# Sheet1.net
KiCad netlist of a schematic drawn in Altium Designer
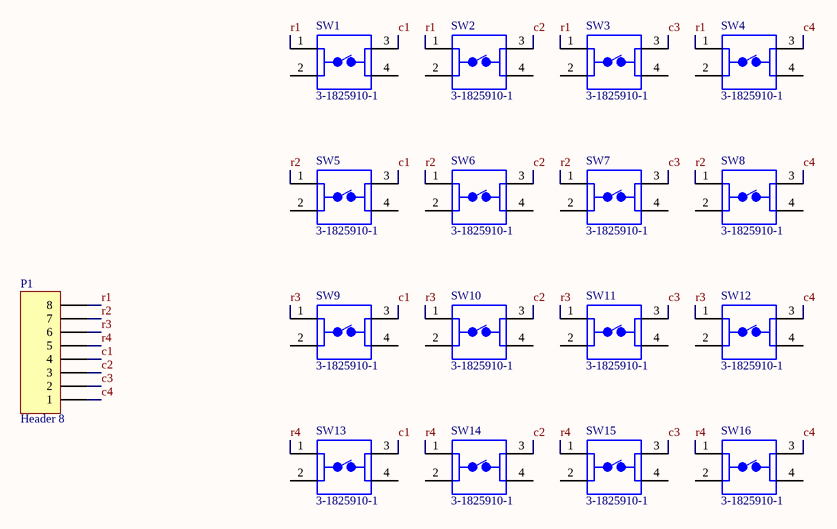
[diagram p0: Sheet1.SchDoc]

(export (version "E")
  (design (tool "Eeschema 10.0.6"))
  (components
    (comp (ref "P1")
      (value "Header 8")
      (footprint "HDR1X8")
      (description "Header, 8-Pin")
      (fields (field (name "PUBLISHER") "Altium Limited"))
      (libsource (lib "Miscellaneous Connectors") (part "Header 8"))
    )
    (comp (ref "SW1")
      (value "3-1825910-1")
      (footprint "TE_3-1825910-1")
      (description "Switch Push Button OFF _ON_ SPST Round Button 0.05A 24VDC Momentary Contact PC Pins Thru-Hole")
      (fields (field (name "MF") "TE Connectivity"))
      (libsource (lib "Schlib1") (part "3-1825910-1"))
    )
    (comp (ref "SW2")
      (value "3-1825910-1")
      (footprint "TE_3-1825910-1")
      (description "Switch Push Button OFF _ON_ SPST Round Button 0.05A 24VDC Momentary Contact PC Pins Thru-Hole")
      (fields (field (name "MF") "TE Connectivity"))
      (libsource (lib "Schlib1") (part "3-1825910-1"))
    )
    (comp (ref "SW3")
      (value "3-1825910-1")
      (footprint "TE_3-1825910-1")
      (description "Switch Push Button OFF _ON_ SPST Round Button 0.05A 24VDC Momentary Contact PC Pins Thru-Hole")
      (fields (field (name "MF") "TE Connectivity"))
      (libsource (lib "Schlib1") (part "3-1825910-1"))
    )
    (comp (ref "SW4")
      (value "3-1825910-1")
      (footprint "TE_3-1825910-1")
      (description "Switch Push Button OFF _ON_ SPST Round Button 0.05A 24VDC Momentary Contact PC Pins Thru-Hole")
      (fields (field (name "MF") "TE Connectivity"))
      (libsource (lib "Schlib1") (part "3-1825910-1"))
    )
    (comp (ref "SW5")
      (value "3-1825910-1")
      (footprint "TE_3-1825910-1")
      (description "Switch Push Button OFF _ON_ SPST Round Button 0.05A 24VDC Momentary Contact PC Pins Thru-Hole")
      (fields (field (name "MF") "TE Connectivity"))
      (libsource (lib "Schlib1") (part "3-1825910-1"))
    )
    (comp (ref "SW6")
      (value "3-1825910-1")
      (footprint "TE_3-1825910-1")
      (description "Switch Push Button OFF _ON_ SPST Round Button 0.05A 24VDC Momentary Contact PC Pins Thru-Hole")
      (fields (field (name "MF") "TE Connectivity"))
      (libsource (lib "Schlib1") (part "3-1825910-1"))
    )
    (comp (ref "SW7")
      (value "3-1825910-1")
      (footprint "TE_3-1825910-1")
      (description "Switch Push Button OFF _ON_ SPST Round Button 0.05A 24VDC Momentary Contact PC Pins Thru-Hole")
      (fields (field (name "MF") "TE Connectivity"))
      (libsource (lib "Schlib1") (part "3-1825910-1"))
    )
    (comp (ref "SW8")
      (value "3-1825910-1")
      (footprint "TE_3-1825910-1")
      (description "Switch Push Button OFF _ON_ SPST Round Button 0.05A 24VDC Momentary Contact PC Pins Thru-Hole")
      (fields (field (name "MF") "TE Connectivity"))
      (libsource (lib "Schlib1") (part "3-1825910-1"))
    )
    (comp (ref "SW9")
      (value "3-1825910-1")
      (footprint "TE_3-1825910-1")
      (description "Switch Push Button OFF _ON_ SPST Round Button 0.05A 24VDC Momentary Contact PC Pins Thru-Hole")
      (fields (field (name "MF") "TE Connectivity"))
      (libsource (lib "Schlib1") (part "3-1825910-1"))
    )
    (comp (ref "SW10")
      (value "3-1825910-1")
      (footprint "TE_3-1825910-1")
      (description "Switch Push Button OFF _ON_ SPST Round Button 0.05A 24VDC Momentary Contact PC Pins Thru-Hole")
      (fields (field (name "MF") "TE Connectivity"))
      (libsource (lib "Schlib1") (part "3-1825910-1"))
    )
    (comp (ref "SW11")
      (value "3-1825910-1")
      (footprint "TE_3-1825910-1")
      (description "Switch Push Button OFF _ON_ SPST Round Button 0.05A 24VDC Momentary Contact PC Pins Thru-Hole")
      (fields (field (name "MF") "TE Connectivity"))
      (libsource (lib "Schlib1") (part "3-1825910-1"))
    )
    (comp (ref "SW12")
      (value "3-1825910-1")
      (footprint "TE_3-1825910-1")
      (description "Switch Push Button OFF _ON_ SPST Round Button 0.05A 24VDC Momentary Contact PC Pins Thru-Hole")
      (fields (field (name "MF") "TE Connectivity"))
      (libsource (lib "Schlib1") (part "3-1825910-1"))
    )
    (comp (ref "SW13")
      (value "3-1825910-1")
      (footprint "TE_3-1825910-1")
      (description "Switch Push Button OFF _ON_ SPST Round Button 0.05A 24VDC Momentary Contact PC Pins Thru-Hole")
      (fields (field (name "MF") "TE Connectivity"))
      (libsource (lib "Schlib1") (part "3-1825910-1"))
    )
    (comp (ref "SW14")
      (value "3-1825910-1")
      (footprint "TE_3-1825910-1")
      (description "Switch Push Button OFF _ON_ SPST Round Button 0.05A 24VDC Momentary Contact PC Pins Thru-Hole")
      (fields (field (name "MF") "TE Connectivity"))
      (libsource (lib "Schlib1") (part "3-1825910-1"))
    )
    (comp (ref "SW15")
      (value "3-1825910-1")
      (footprint "TE_3-1825910-1")
      (description "Switch Push Button OFF _ON_ SPST Round Button 0.05A 24VDC Momentary Contact PC Pins Thru-Hole")
      (fields (field (name "MF") "TE Connectivity"))
      (libsource (lib "Schlib1") (part "3-1825910-1"))
    )
    (comp (ref "SW16")
      (value "3-1825910-1")
      (footprint "TE_3-1825910-1")
      (description "Switch Push Button OFF _ON_ SPST Round Button 0.05A 24VDC Momentary Contact PC Pins Thru-Hole")
      (fields (field (name "MF") "TE Connectivity"))
      (libsource (lib "Schlib1") (part "3-1825910-1"))
    )
  )
  (nets
    (net (code "1") (name "/c1") (class "Default")
      (node (ref "P1") (pin "4") (pinfunction "4_4") (pintype "passive"))
      (node (ref "SW1") (pin "3") (pinfunction "3_3") (pintype "passive"))
      (node (ref "SW13") (pin "3") (pinfunction "3_3") (pintype "passive"))
      (node (ref "SW5") (pin "3") (pinfunction "3_3") (pintype "passive"))
      (node (ref "SW9") (pin "3") (pinfunction "3_3") (pintype "passive"))
    )
    (net (code "2") (name "/c2") (class "Default")
      (node (ref "P1") (pin "3") (pinfunction "3_3") (pintype "passive"))
      (node (ref "SW10") (pin "3") (pinfunction "3_3") (pintype "passive"))
      (node (ref "SW14") (pin "3") (pinfunction "3_3") (pintype "passive"))
      (node (ref "SW2") (pin "3") (pinfunction "3_3") (pintype "passive"))
      (node (ref "SW6") (pin "3") (pinfunction "3_3") (pintype "passive"))
    )
    (net (code "3") (name "/c3") (class "Default")
      (node (ref "P1") (pin "2") (pinfunction "2_2") (pintype "passive"))
      (node (ref "SW11") (pin "3") (pinfunction "3_3") (pintype "passive"))
      (node (ref "SW15") (pin "3") (pinfunction "3_3") (pintype "passive"))
      (node (ref "SW3") (pin "3") (pinfunction "3_3") (pintype "passive"))
      (node (ref "SW7") (pin "3") (pinfunction "3_3") (pintype "passive"))
    )
    (net (code "4") (name "/c4") (class "Default")
      (node (ref "P1") (pin "1") (pinfunction "1_1") (pintype "passive"))
      (node (ref "SW12") (pin "3") (pinfunction "3_3") (pintype "passive"))
      (node (ref "SW16") (pin "3") (pinfunction "3_3") (pintype "passive"))
      (node (ref "SW4") (pin "3") (pinfunction "3_3") (pintype "passive"))
      (node (ref "SW8") (pin "3") (pinfunction "3_3") (pintype "passive"))
    )
    (net (code "5") (name "/r1") (class "Default")
      (node (ref "P1") (pin "8") (pinfunction "8_8") (pintype "passive"))
      (node (ref "SW1") (pin "1") (pinfunction "1_1") (pintype "passive"))
      (node (ref "SW2") (pin "1") (pinfunction "1_1") (pintype "passive"))
      (node (ref "SW3") (pin "1") (pinfunction "1_1") (pintype "passive"))
      (node (ref "SW4") (pin "1") (pinfunction "1_1") (pintype "passive"))
    )
    (net (code "6") (name "/r2") (class "Default")
      (node (ref "P1") (pin "7") (pinfunction "7_7") (pintype "passive"))
      (node (ref "SW5") (pin "1") (pinfunction "1_1") (pintype "passive"))
      (node (ref "SW6") (pin "1") (pinfunction "1_1") (pintype "passive"))
      (node (ref "SW7") (pin "1") (pinfunction "1_1") (pintype "passive"))
      (node (ref "SW8") (pin "1") (pinfunction "1_1") (pintype "passive"))
    )
    (net (code "7") (name "/r3") (class "Default")
      (node (ref "P1") (pin "6") (pinfunction "6_6") (pintype "passive"))
      (node (ref "SW10") (pin "1") (pinfunction "1_1") (pintype "passive"))
      (node (ref "SW11") (pin "1") (pinfunction "1_1") (pintype "passive"))
      (node (ref "SW12") (pin "1") (pinfunction "1_1") (pintype "passive"))
      (node (ref "SW9") (pin "1") (pinfunction "1_1") (pintype "passive"))
    )
    (net (code "8") (name "/r4") (class "Default")
      (node (ref "P1") (pin "5") (pinfunction "5_5") (pintype "passive"))
      (node (ref "SW13") (pin "1") (pinfunction "1_1") (pintype "passive"))
      (node (ref "SW14") (pin "1") (pinfunction "1_1") (pintype "passive"))
      (node (ref "SW15") (pin "1") (pinfunction "1_1") (pintype "passive"))
      (node (ref "SW16") (pin "1") (pinfunction "1_1") (pintype "passive"))
    )
    (net (code "9") (name "unconnected-(SW1-Pad2)") (class "Default")
      (node (ref "SW1") (pin "2") (pinfunction "2_2") (pintype "passive"))
    )
    (net (code "10") (name "unconnected-(SW1-Pad4)") (class "Default")
      (node (ref "SW1") (pin "4") (pinfunction "4_4") (pintype "passive"))
    )
    (net (code "11") (name "unconnected-(SW2-Pad2)") (class "Default")
      (node (ref "SW2") (pin "2") (pinfunction "2_2") (pintype "passive"))
    )
    (net (code "12") (name "unconnected-(SW2-Pad4)") (class "Default")
      (node (ref "SW2") (pin "4") (pinfunction "4_4") (pintype "passive"))
    )
    (net (code "13") (name "unconnected-(SW3-Pad2)") (class "Default")
      (node (ref "SW3") (pin "2") (pinfunction "2_2") (pintype "passive"))
    )
    (net (code "14") (name "unconnected-(SW3-Pad4)") (class "Default")
      (node (ref "SW3") (pin "4") (pinfunction "4_4") (pintype "passive"))
    )
    (net (code "15") (name "unconnected-(SW4-Pad2)") (class "Default")
      (node (ref "SW4") (pin "2") (pinfunction "2_2") (pintype "passive"))
    )
    (net (code "16") (name "unconnected-(SW4-Pad4)") (class "Default")
      (node (ref "SW4") (pin "4") (pinfunction "4_4") (pintype "passive"))
    )
    (net (code "17") (name "unconnected-(SW5-Pad2)") (class "Default")
      (node (ref "SW5") (pin "2") (pinfunction "2_2") (pintype "passive"))
    )
    (net (code "18") (name "unconnected-(SW5-Pad4)") (class "Default")
      (node (ref "SW5") (pin "4") (pinfunction "4_4") (pintype "passive"))
    )
    (net (code "19") (name "unconnected-(SW6-Pad2)") (class "Default")
      (node (ref "SW6") (pin "2") (pinfunction "2_2") (pintype "passive"))
    )
    (net (code "20") (name "unconnected-(SW6-Pad4)") (class "Default")
      (node (ref "SW6") (pin "4") (pinfunction "4_4") (pintype "passive"))
    )
    (net (code "21") (name "unconnected-(SW7-Pad2)") (class "Default")
      (node (ref "SW7") (pin "2") (pinfunction "2_2") (pintype "passive"))
    )
    (net (code "22") (name "unconnected-(SW7-Pad4)") (class "Default")
      (node (ref "SW7") (pin "4") (pinfunction "4_4") (pintype "passive"))
    )
    (net (code "23") (name "unconnected-(SW8-Pad2)") (class "Default")
      (node (ref "SW8") (pin "2") (pinfunction "2_2") (pintype "passive"))
    )
    (net (code "24") (name "unconnected-(SW8-Pad4)") (class "Default")
      (node (ref "SW8") (pin "4") (pinfunction "4_4") (pintype "passive"))
    )
    (net (code "25") (name "unconnected-(SW9-Pad2)") (class "Default")
      (node (ref "SW9") (pin "2") (pinfunction "2_2") (pintype "passive"))
    )
    (net (code "26") (name "unconnected-(SW9-Pad4)") (class "Default")
      (node (ref "SW9") (pin "4") (pinfunction "4_4") (pintype "passive"))
    )
    (net (code "27") (name "unconnected-(SW10-Pad2)") (class "Default")
      (node (ref "SW10") (pin "2") (pinfunction "2_2") (pintype "passive"))
    )
    (net (code "28") (name "unconnected-(SW10-Pad4)") (class "Default")
      (node (ref "SW10") (pin "4") (pinfunction "4_4") (pintype "passive"))
    )
    (net (code "29") (name "unconnected-(SW11-Pad2)") (class "Default")
      (node (ref "SW11") (pin "2") (pinfunction "2_2") (pintype "passive"))
    )
    (net (code "30") (name "unconnected-(SW11-Pad4)") (class "Default")
      (node (ref "SW11") (pin "4") (pinfunction "4_4") (pintype "passive"))
    )
    (net (code "31") (name "unconnected-(SW12-Pad2)") (class "Default")
      (node (ref "SW12") (pin "2") (pinfunction "2_2") (pintype "passive"))
    )
    (net (code "32") (name "unconnected-(SW12-Pad4)") (class "Default")
      (node (ref "SW12") (pin "4") (pinfunction "4_4") (pintype "passive"))
    )
    (net (code "33") (name "unconnected-(SW13-Pad2)") (class "Default")
      (node (ref "SW13") (pin "2") (pinfunction "2_2") (pintype "passive"))
    )
    (net (code "34") (name "unconnected-(SW13-Pad4)") (class "Default")
      (node (ref "SW13") (pin "4") (pinfunction "4_4") (pintype "passive"))
    )
    (net (code "35") (name "unconnected-(SW14-Pad2)") (class "Default")
      (node (ref "SW14") (pin "2") (pinfunction "2_2") (pintype "passive"))
    )
    (net (code "36") (name "unconnected-(SW14-Pad4)") (class "Default")
      (node (ref "SW14") (pin "4") (pinfunction "4_4") (pintype "passive"))
    )
    (net (code "37") (name "unconnected-(SW15-Pad2)") (class "Default")
      (node (ref "SW15") (pin "2") (pinfunction "2_2") (pintype "passive"))
    )
    (net (code "38") (name "unconnected-(SW15-Pad4)") (class "Default")
      (node (ref "SW15") (pin "4") (pinfunction "4_4") (pintype "passive"))
    )
    (net (code "39") (name "unconnected-(SW16-Pad2)") (class "Default")
      (node (ref "SW16") (pin "2") (pinfunction "2_2") (pintype "passive"))
    )
    (net (code "40") (name "unconnected-(SW16-Pad4)") (class "Default")
      (node (ref "SW16") (pin "4") (pinfunction "4_4") (pintype "passive"))
    )
  )
)
